# M109A.net
KiCad netlist of a schematic drawn in EAGLE
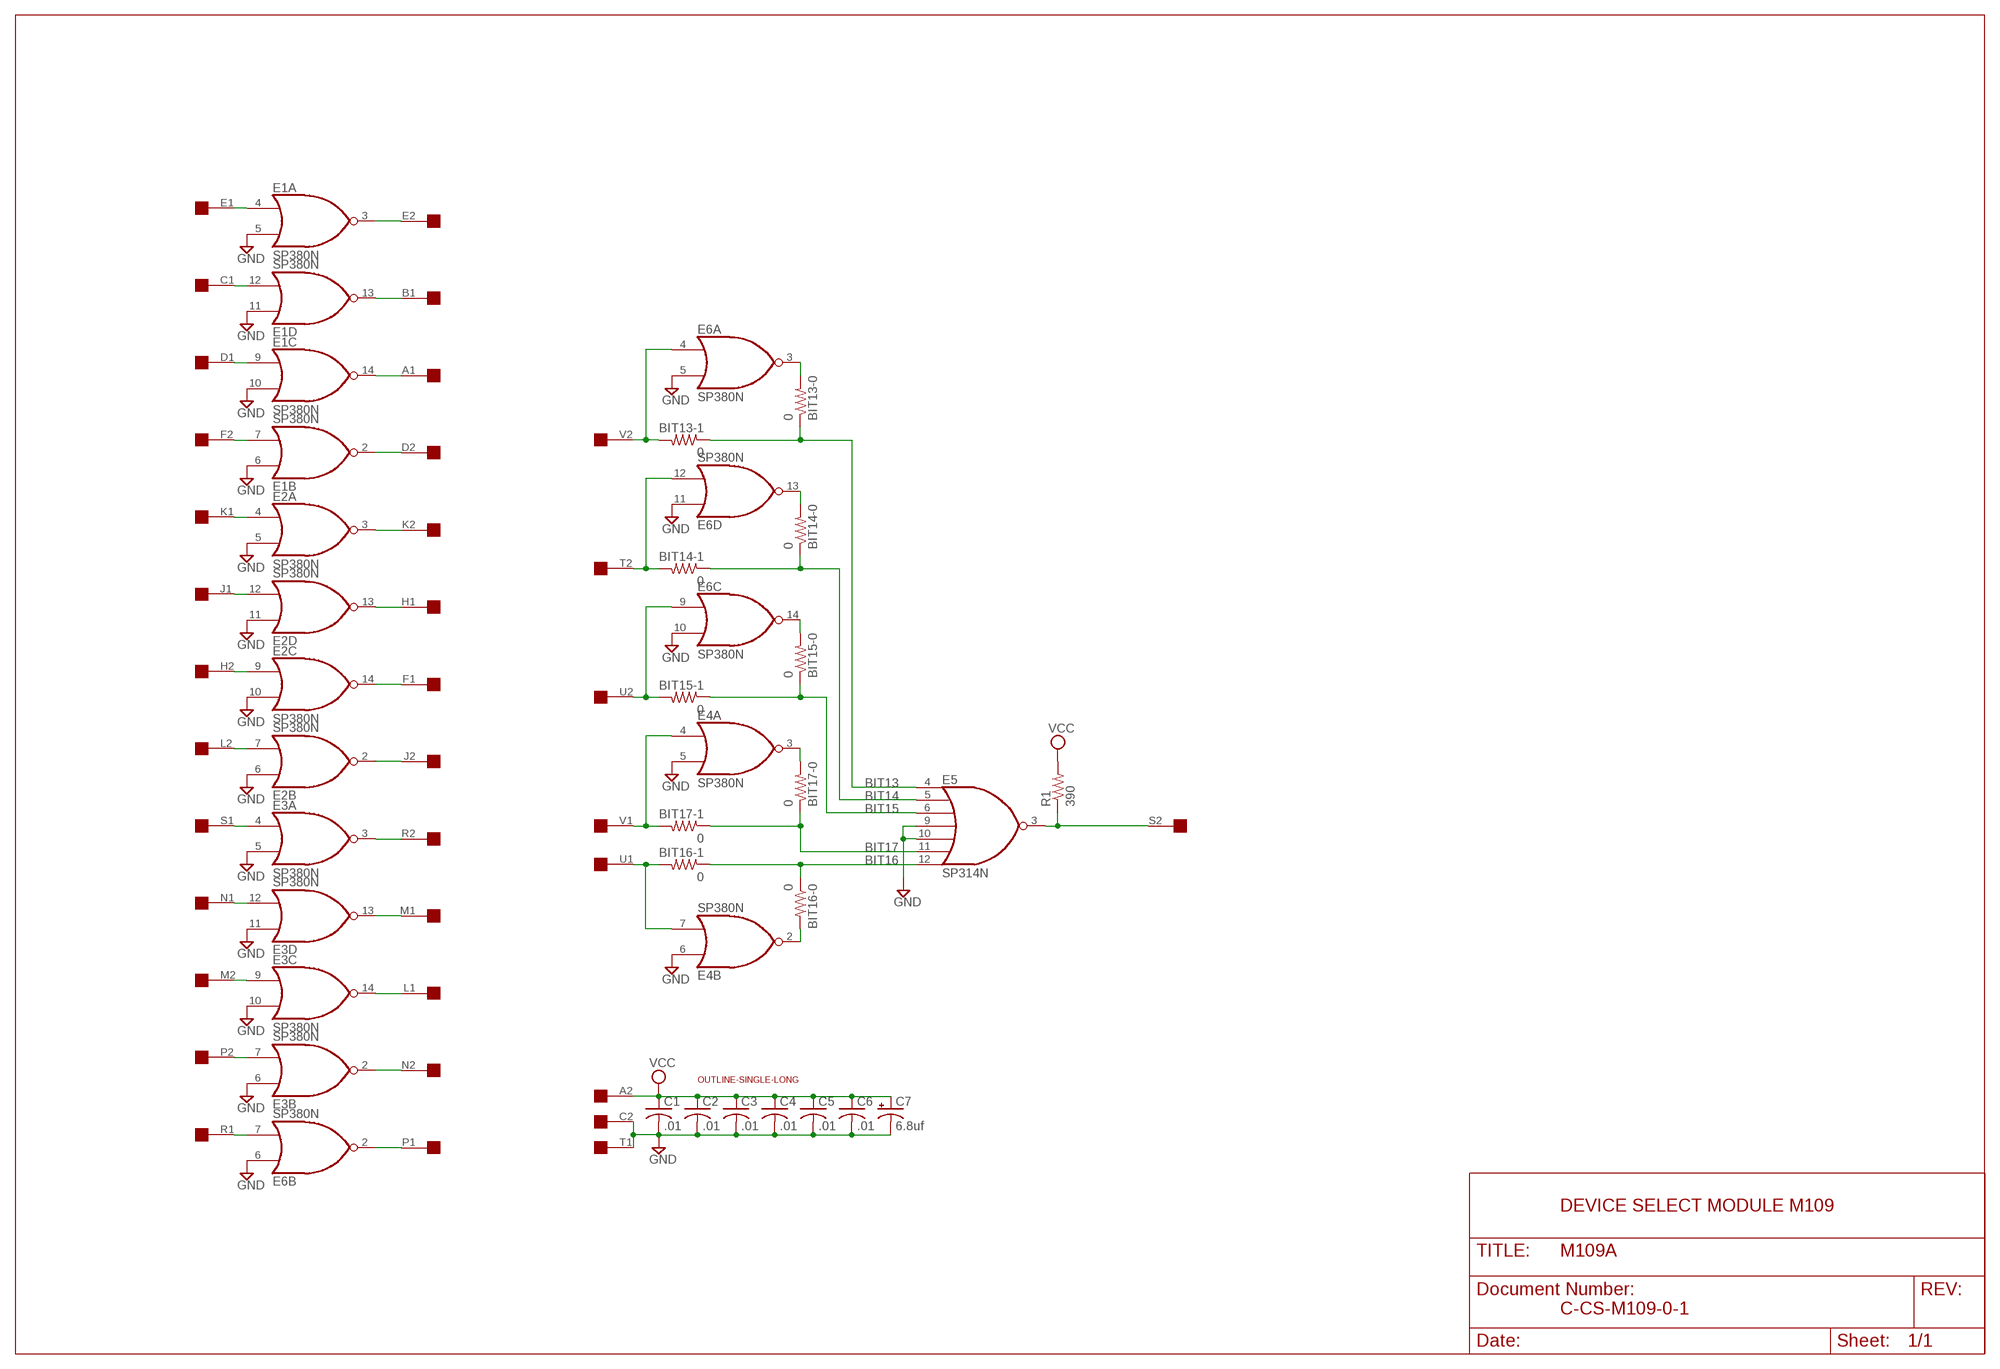
[diagram p0: schematic, sheet 1]

(export (version "E")
  (design (tool "Eeschema 10.0.6"))
  (components
    (comp (ref "BIT13-0")
      (value "0")
      (footprint "eagle-import:0207_10")
      (libsource (lib "eagle-import") (part "R-US_0207/10"))
    )
    (comp (ref "BIT13-1")
      (value "0")
      (footprint "eagle-import:0207_10")
      (libsource (lib "eagle-import") (part "R-US_0207/10"))
    )
    (comp (ref "BIT14-0")
      (value "0")
      (footprint "eagle-import:0207_10")
      (libsource (lib "eagle-import") (part "R-US_0207/10"))
    )
    (comp (ref "BIT14-1")
      (value "0")
      (footprint "eagle-import:0207_10")
      (libsource (lib "eagle-import") (part "R-US_0207/10"))
    )
    (comp (ref "BIT15-0")
      (value "0")
      (footprint "eagle-import:0207_10")
      (libsource (lib "eagle-import") (part "R-US_0207/10"))
    )
    (comp (ref "BIT15-1")
      (value "0")
      (footprint "eagle-import:0207_10")
      (libsource (lib "eagle-import") (part "R-US_0207/10"))
    )
    (comp (ref "BIT16-0")
      (value "0")
      (footprint "eagle-import:0207_10")
      (libsource (lib "eagle-import") (part "R-US_0207/10"))
    )
    (comp (ref "BIT16-1")
      (value "0")
      (footprint "eagle-import:0207_10")
      (libsource (lib "eagle-import") (part "R-US_0207/10"))
    )
    (comp (ref "BIT17-0")
      (value "0")
      (footprint "eagle-import:0207_10")
      (libsource (lib "eagle-import") (part "R-US_0207/10"))
    )
    (comp (ref "BIT17-1")
      (value "0")
      (footprint "eagle-import:0207_10")
      (libsource (lib "eagle-import") (part "R-US_0207/10"))
    )
    (comp (ref "C1")
      (value ".01")
      (footprint "eagle-import:C050-025X075")
      (libsource (lib "eagle-import") (part "C-US050-025X075"))
    )
    (comp (ref "C2")
      (value ".01")
      (footprint "eagle-import:C050-025X075")
      (libsource (lib "eagle-import") (part "C-US050-025X075"))
    )
    (comp (ref "C3")
      (value ".01")
      (footprint "eagle-import:C050-025X075")
      (libsource (lib "eagle-import") (part "C-US050-025X075"))
    )
    (comp (ref "C4")
      (value ".01")
      (footprint "eagle-import:C050-025X075")
      (libsource (lib "eagle-import") (part "C-US050-025X075"))
    )
    (comp (ref "C5")
      (value ".01")
      (footprint "eagle-import:C050-025X075")
      (libsource (lib "eagle-import") (part "C-US050-025X075"))
    )
    (comp (ref "C6")
      (value ".01")
      (footprint "eagle-import:C050-025X075")
      (libsource (lib "eagle-import") (part "C-US050-025X075"))
    )
    (comp (ref "C7")
      (value "6.8uf")
      (footprint "eagle-import:E22-6")
      (libsource (lib "eagle-import") (part "CPOL-USE22-6AXIAL"))
    )
    (comp (ref "E1")
      (value "SP380N")
      (footprint "eagle-import:DIL14")
      (libsource (lib "eagle-import") (part "SP380N"))
    )
    (comp (ref "E2")
      (value "SP380N")
      (footprint "eagle-import:DIL14")
      (libsource (lib "eagle-import") (part "SP380N"))
    )
    (comp (ref "E3")
      (value "SP380N")
      (footprint "eagle-import:DIL14")
      (libsource (lib "eagle-import") (part "SP380N"))
    )
    (comp (ref "E4")
      (value "SP380N")
      (footprint "eagle-import:DIL14")
      (libsource (lib "eagle-import") (part "SP380N"))
    )
    (comp (ref "E5")
      (value "SP314N")
      (footprint "eagle-import:DIL14")
      (libsource (lib "eagle-import") (part "SP314N"))
    )
    (comp (ref "E6")
      (value "SP380N")
      (footprint "eagle-import:DIL14")
      (libsource (lib "eagle-import") (part "SP380N"))
    )
    (comp (ref "R1")
      (value "390")
      (footprint "eagle-import:0207_10")
      (libsource (lib "eagle-import") (part "R-US_0207/10"))
    )
    (comp (ref "U$1")
      (value "SINGLE")
      (footprint "eagle-import:EDGE-CON2")
      (libsource (lib "eagle-import") (part "SINGLE"))
    )
    (comp (ref "U$2")
      (value "OUTLINE-SINGLE-LONG")
      (footprint "eagle-import:SINGLE-LONG")
      (libsource (lib "eagle-import") (part "OUTLINE-SINGLE-LONG"))
    )
  )
  (nets
    (net (code "1") (name "/BIT13") (class "Default")
      (node (ref "BIT13-0") (pin "1") (pinfunction "1_1") (pintype "passive"))
      (node (ref "BIT13-1") (pin "1") (pinfunction "1_1") (pintype "passive"))
      (node (ref "E5") (pin "4") (pinfunction "I0_4") (pintype "input"))
    )
    (net (code "2") (name "/BIT14") (class "Default")
      (node (ref "BIT14-0") (pin "1") (pinfunction "1_1") (pintype "passive"))
      (node (ref "BIT14-1") (pin "1") (pinfunction "1_1") (pintype "passive"))
      (node (ref "E5") (pin "5") (pinfunction "I1_5") (pintype "input"))
    )
    (net (code "3") (name "/BIT15") (class "Default")
      (node (ref "BIT15-0") (pin "1") (pinfunction "1_1") (pintype "passive"))
      (node (ref "BIT15-1") (pin "1") (pinfunction "1_1") (pintype "passive"))
      (node (ref "E5") (pin "6") (pinfunction "I2_6") (pintype "input"))
    )
    (net (code "4") (name "/BIT16") (class "Default")
      (node (ref "BIT16-0") (pin "1") (pinfunction "1_1") (pintype "passive"))
      (node (ref "BIT16-1") (pin "1") (pinfunction "1_1") (pintype "passive"))
      (node (ref "E5") (pin "12") (pinfunction "I6_12") (pintype "input"))
    )
    (net (code "5") (name "/BIT17") (class "Default")
      (node (ref "BIT17-0") (pin "1") (pinfunction "1_1") (pintype "passive"))
      (node (ref "BIT17-1") (pin "1") (pinfunction "1_1") (pintype "passive"))
      (node (ref "E5") (pin "11") (pinfunction "I5_11") (pintype "input"))
    )
    (net (code "6") (name "GND") (class "Default")
      (node (ref "C1") (pin "2") (pinfunction "2_2") (pintype "passive"))
      (node (ref "C2") (pin "2") (pinfunction "2_2") (pintype "passive"))
      (node (ref "C3") (pin "2") (pinfunction "2_2") (pintype "passive"))
      (node (ref "C4") (pin "2") (pinfunction "2_2") (pintype "passive"))
      (node (ref "C5") (pin "2") (pinfunction "2_2") (pintype "passive"))
      (node (ref "C6") (pin "2") (pinfunction "2_2") (pintype "passive"))
      (node (ref "C7") (pin "-") (pinfunction "-_-") (pintype "passive"))
      (node (ref "E1") (pin "10") (pinfunction "I1_10") (pintype "input"))
      (node (ref "E1") (pin "11") (pinfunction "I0_11") (pintype "input"))
      (node (ref "E1") (pin "5") (pinfunction "I1_5") (pintype "input"))
      (node (ref "E1") (pin "6") (pinfunction "I0_6") (pintype "input"))
      (node (ref "E2") (pin "10") (pinfunction "I1_10") (pintype "input"))
      (node (ref "E2") (pin "11") (pinfunction "I0_11") (pintype "input"))
      (node (ref "E2") (pin "5") (pinfunction "I1_5") (pintype "input"))
      (node (ref "E2") (pin "6") (pinfunction "I0_6") (pintype "input"))
      (node (ref "E3") (pin "10") (pinfunction "I1_10") (pintype "input"))
      (node (ref "E3") (pin "11") (pinfunction "I0_11") (pintype "input"))
      (node (ref "E3") (pin "5") (pinfunction "I1_5") (pintype "input"))
      (node (ref "E3") (pin "6") (pinfunction "I0_6") (pintype "input"))
      (node (ref "E4") (pin "5") (pinfunction "I1_5") (pintype "input"))
      (node (ref "E4") (pin "6") (pinfunction "I0_6") (pintype "input"))
      (node (ref "E5") (pin "10") (pinfunction "I4_10") (pintype "input"))
      (node (ref "E5") (pin "9") (pinfunction "I3_9") (pintype "input"))
      (node (ref "E6") (pin "10") (pinfunction "I1_10") (pintype "input"))
      (node (ref "E6") (pin "11") (pinfunction "I0_11") (pintype "input"))
      (node (ref "E6") (pin "5") (pinfunction "I1_5") (pintype "input"))
      (node (ref "E6") (pin "6") (pinfunction "I0_6") (pintype "input"))
      (node (ref "U$1") (pin "C2") (pinfunction "1_C2") (pintype "bidirectional"))
      (node (ref "U$1") (pin "T1") (pinfunction "1_T1") (pintype "bidirectional"))
    )
    (net (code "7") (name "Net-(E1A-I0)") (class "Default")
      (node (ref "E1") (pin "4") (pinfunction "I0_4") (pintype "input"))
      (node (ref "U$1") (pin "E1") (pinfunction "1_E1") (pintype "bidirectional"))
    )
    (net (code "8") (name "Net-(E1A-O)") (class "Default")
      (node (ref "E1") (pin "3") (pinfunction "O_3") (pintype "output"))
      (node (ref "U$1") (pin "E2") (pinfunction "1_E2") (pintype "bidirectional"))
    )
    (net (code "9") (name "Net-(E1B-I1)") (class "Default")
      (node (ref "E1") (pin "7") (pinfunction "I1_7") (pintype "input"))
      (node (ref "U$1") (pin "F2") (pinfunction "1_F2") (pintype "bidirectional"))
    )
    (net (code "10") (name "Net-(E1B-O)") (class "Default")
      (node (ref "E1") (pin "2") (pinfunction "O_2") (pintype "output"))
      (node (ref "U$1") (pin "D2") (pinfunction "1_D2") (pintype "bidirectional"))
    )
    (net (code "11") (name "Net-(E1C-I0)") (class "Default")
      (node (ref "E1") (pin "9") (pinfunction "I0_9") (pintype "input"))
      (node (ref "U$1") (pin "D1") (pinfunction "1_D1") (pintype "bidirectional"))
    )
    (net (code "12") (name "Net-(E1C-O)") (class "Default")
      (node (ref "E1") (pin "14") (pinfunction "O_14") (pintype "output"))
      (node (ref "U$1") (pin "A1") (pinfunction "1_A1") (pintype "bidirectional"))
    )
    (net (code "13") (name "Net-(E1D-I1)") (class "Default")
      (node (ref "E1") (pin "12") (pinfunction "I1_12") (pintype "input"))
      (node (ref "U$1") (pin "C1") (pinfunction "1_C1") (pintype "bidirectional"))
    )
    (net (code "14") (name "Net-(E1D-O)") (class "Default")
      (node (ref "E1") (pin "13") (pinfunction "O_13") (pintype "output"))
      (node (ref "U$1") (pin "B1") (pinfunction "1_B1") (pintype "bidirectional"))
    )
    (net (code "15") (name "Net-(E2A-I0)") (class "Default")
      (node (ref "E2") (pin "4") (pinfunction "I0_4") (pintype "input"))
      (node (ref "U$1") (pin "K1") (pinfunction "1_K1") (pintype "bidirectional"))
    )
    (net (code "16") (name "Net-(E2A-O)") (class "Default")
      (node (ref "E2") (pin "3") (pinfunction "O_3") (pintype "output"))
      (node (ref "U$1") (pin "K2") (pinfunction "1_K2") (pintype "bidirectional"))
    )
    (net (code "17") (name "Net-(E2B-I1)") (class "Default")
      (node (ref "E2") (pin "7") (pinfunction "I1_7") (pintype "input"))
      (node (ref "U$1") (pin "L2") (pinfunction "1_L2") (pintype "bidirectional"))
    )
    (net (code "18") (name "Net-(E2B-O)") (class "Default")
      (node (ref "E2") (pin "2") (pinfunction "O_2") (pintype "output"))
      (node (ref "U$1") (pin "J2") (pinfunction "1_J2") (pintype "bidirectional"))
    )
    (net (code "19") (name "Net-(E2C-I0)") (class "Default")
      (node (ref "E2") (pin "9") (pinfunction "I0_9") (pintype "input"))
      (node (ref "U$1") (pin "H2") (pinfunction "1_H2") (pintype "bidirectional"))
    )
    (net (code "20") (name "Net-(E2C-O)") (class "Default")
      (node (ref "E2") (pin "14") (pinfunction "O_14") (pintype "output"))
      (node (ref "U$1") (pin "F1") (pinfunction "1_F1") (pintype "bidirectional"))
    )
    (net (code "21") (name "Net-(E2D-I1)") (class "Default")
      (node (ref "E2") (pin "12") (pinfunction "I1_12") (pintype "input"))
      (node (ref "U$1") (pin "J1") (pinfunction "1_J1") (pintype "bidirectional"))
    )
    (net (code "22") (name "Net-(E2D-O)") (class "Default")
      (node (ref "E2") (pin "13") (pinfunction "O_13") (pintype "output"))
      (node (ref "U$1") (pin "H1") (pinfunction "1_H1") (pintype "bidirectional"))
    )
    (net (code "23") (name "Net-(E3A-I0)") (class "Default")
      (node (ref "E3") (pin "4") (pinfunction "I0_4") (pintype "input"))
      (node (ref "U$1") (pin "S1") (pinfunction "1_S1") (pintype "bidirectional"))
    )
    (net (code "24") (name "Net-(E3A-O)") (class "Default")
      (node (ref "E3") (pin "3") (pinfunction "O_3") (pintype "output"))
      (node (ref "U$1") (pin "R2") (pinfunction "1_R2") (pintype "bidirectional"))
    )
    (net (code "25") (name "Net-(E3B-I1)") (class "Default")
      (node (ref "E3") (pin "7") (pinfunction "I1_7") (pintype "input"))
      (node (ref "U$1") (pin "P2") (pinfunction "1_P2") (pintype "bidirectional"))
    )
    (net (code "26") (name "Net-(E3B-O)") (class "Default")
      (node (ref "E3") (pin "2") (pinfunction "O_2") (pintype "output"))
      (node (ref "U$1") (pin "N2") (pinfunction "1_N2") (pintype "bidirectional"))
    )
    (net (code "27") (name "Net-(E3C-I0)") (class "Default")
      (node (ref "E3") (pin "9") (pinfunction "I0_9") (pintype "input"))
      (node (ref "U$1") (pin "M2") (pinfunction "1_M2") (pintype "bidirectional"))
    )
    (net (code "28") (name "Net-(E3C-O)") (class "Default")
      (node (ref "E3") (pin "14") (pinfunction "O_14") (pintype "output"))
      (node (ref "U$1") (pin "L1") (pinfunction "1_L1") (pintype "bidirectional"))
    )
    (net (code "29") (name "Net-(E3D-I1)") (class "Default")
      (node (ref "E3") (pin "12") (pinfunction "I1_12") (pintype "input"))
      (node (ref "U$1") (pin "N1") (pinfunction "1_N1") (pintype "bidirectional"))
    )
    (net (code "30") (name "Net-(E3D-O)") (class "Default")
      (node (ref "E3") (pin "13") (pinfunction "O_13") (pintype "output"))
      (node (ref "U$1") (pin "M1") (pinfunction "1_M1") (pintype "bidirectional"))
    )
    (net (code "31") (name "Net-(E4A-I0)") (class "Default")
      (node (ref "BIT17-1") (pin "2") (pinfunction "2_2") (pintype "passive"))
      (node (ref "E4") (pin "4") (pinfunction "I0_4") (pintype "input"))
      (node (ref "U$1") (pin "V1") (pinfunction "1_V1") (pintype "bidirectional"))
    )
    (net (code "32") (name "Net-(E4A-O)") (class "Default")
      (node (ref "BIT17-0") (pin "2") (pinfunction "2_2") (pintype "passive"))
      (node (ref "E4") (pin "3") (pinfunction "O_3") (pintype "output"))
    )
    (net (code "33") (name "Net-(E4B-I1)") (class "Default")
      (node (ref "BIT16-1") (pin "2") (pinfunction "2_2") (pintype "passive"))
      (node (ref "E4") (pin "7") (pinfunction "I1_7") (pintype "input"))
      (node (ref "U$1") (pin "U1") (pinfunction "1_U1") (pintype "bidirectional"))
    )
    (net (code "34") (name "Net-(E4B-O)") (class "Default")
      (node (ref "BIT16-0") (pin "2") (pinfunction "2_2") (pintype "passive"))
      (node (ref "E4") (pin "2") (pinfunction "O_2") (pintype "output"))
    )
    (net (code "35") (name "Net-(E5A-O)") (class "Default")
      (node (ref "E5") (pin "3") (pinfunction "O_3") (pintype "output"))
      (node (ref "R1") (pin "1") (pinfunction "1_1") (pintype "passive"))
      (node (ref "U$1") (pin "S2") (pinfunction "1_S2") (pintype "bidirectional"))
    )
    (net (code "36") (name "Net-(E6A-I0)") (class "Default")
      (node (ref "BIT13-1") (pin "2") (pinfunction "2_2") (pintype "passive"))
      (node (ref "E6") (pin "4") (pinfunction "I0_4") (pintype "input"))
      (node (ref "U$1") (pin "V2") (pinfunction "1_V2") (pintype "bidirectional"))
    )
    (net (code "37") (name "Net-(E6A-O)") (class "Default")
      (node (ref "BIT13-0") (pin "2") (pinfunction "2_2") (pintype "passive"))
      (node (ref "E6") (pin "3") (pinfunction "O_3") (pintype "output"))
    )
    (net (code "38") (name "Net-(E6B-I1)") (class "Default")
      (node (ref "E6") (pin "7") (pinfunction "I1_7") (pintype "input"))
      (node (ref "U$1") (pin "R1") (pinfunction "1_R1") (pintype "bidirectional"))
    )
    (net (code "39") (name "Net-(E6B-O)") (class "Default")
      (node (ref "E6") (pin "2") (pinfunction "O_2") (pintype "output"))
      (node (ref "U$1") (pin "P1") (pinfunction "1_P1") (pintype "bidirectional"))
    )
    (net (code "40") (name "Net-(E6C-I0)") (class "Default")
      (node (ref "BIT15-1") (pin "2") (pinfunction "2_2") (pintype "passive"))
      (node (ref "E6") (pin "9") (pinfunction "I0_9") (pintype "input"))
      (node (ref "U$1") (pin "U2") (pinfunction "1_U2") (pintype "bidirectional"))
    )
    (net (code "41") (name "Net-(E6C-O)") (class "Default")
      (node (ref "BIT15-0") (pin "2") (pinfunction "2_2") (pintype "passive"))
      (node (ref "E6") (pin "14") (pinfunction "O_14") (pintype "output"))
    )
    (net (code "42") (name "Net-(E6D-I1)") (class "Default")
      (node (ref "BIT14-1") (pin "2") (pinfunction "2_2") (pintype "passive"))
      (node (ref "E6") (pin "12") (pinfunction "I1_12") (pintype "input"))
      (node (ref "U$1") (pin "T2") (pinfunction "1_T2") (pintype "bidirectional"))
    )
    (net (code "43") (name "Net-(E6D-O)") (class "Default")
      (node (ref "BIT14-0") (pin "2") (pinfunction "2_2") (pintype "passive"))
      (node (ref "E6") (pin "13") (pinfunction "O_13") (pintype "output"))
    )
    (net (code "44") (name "VCC") (class "Default")
      (node (ref "C1") (pin "1") (pinfunction "1_1") (pintype "passive"))
      (node (ref "C2") (pin "1") (pinfunction "1_1") (pintype "passive"))
      (node (ref "C3") (pin "1") (pinfunction "1_1") (pintype "passive"))
      (node (ref "C4") (pin "1") (pinfunction "1_1") (pintype "passive"))
      (node (ref "C5") (pin "1") (pinfunction "1_1") (pintype "passive"))
      (node (ref "C6") (pin "1") (pinfunction "1_1") (pintype "passive"))
      (node (ref "C7") (pin "+") (pinfunction "+_+") (pintype "passive"))
      (node (ref "R1") (pin "2") (pinfunction "2_2") (pintype "passive"))
      (node (ref "U$1") (pin "A2") (pinfunction "1_A2") (pintype "bidirectional"))
    )
  )
)
